# remote_switch.net
KiCad netlist of a schematic drawn in EAGLE
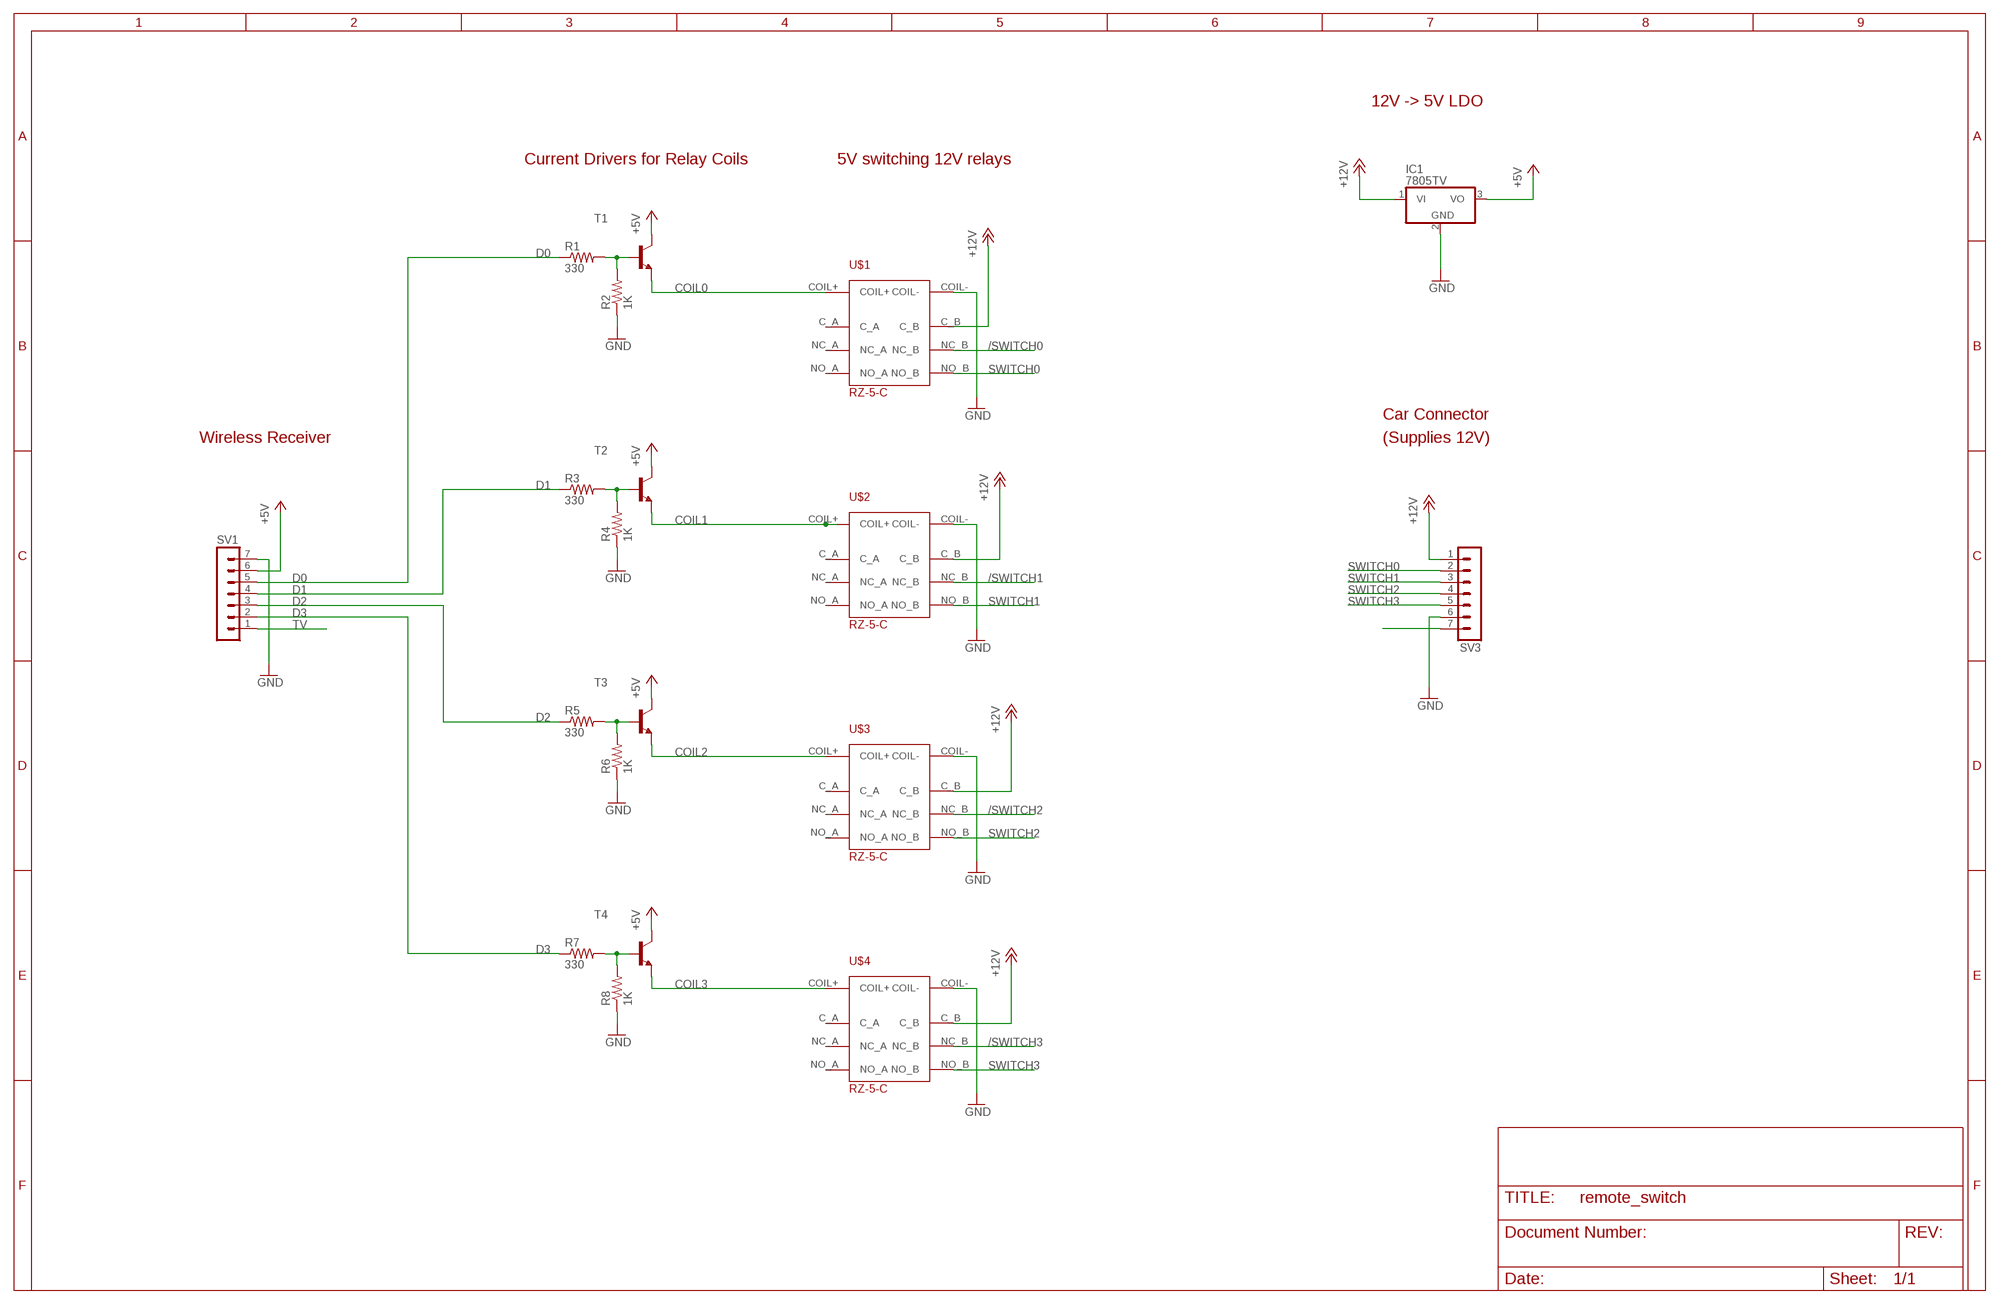
[diagram p0: schematic, sheet 1]

(export (version "E")
  (design (tool "Eeschema 10.0.6"))
  (components
    (comp (ref "IC1")
      (value "7805TV")
      (footprint "eagle-import:TO220V")
      (libsource (lib "eagle-import") (part "78TV05"))
    )
    (comp (ref "R1")
      (value "330")
      (footprint "eagle-import:P0613V")
      (libsource (lib "eagle-import") (part "R-US_0613/5V"))
    )
    (comp (ref "R2")
      (value "1K")
      (footprint "eagle-import:P0613V")
      (libsource (lib "eagle-import") (part "R-US_0613/5V"))
    )
    (comp (ref "R3")
      (value "330")
      (footprint "eagle-import:P0613V")
      (libsource (lib "eagle-import") (part "R-US_0613/5V"))
    )
    (comp (ref "R4")
      (value "1K")
      (footprint "eagle-import:P0613V")
      (libsource (lib "eagle-import") (part "R-US_0613/5V"))
    )
    (comp (ref "R5")
      (value "330")
      (footprint "eagle-import:P0613V")
      (libsource (lib "eagle-import") (part "R-US_0613/5V"))
    )
    (comp (ref "R6")
      (value "1K")
      (footprint "eagle-import:P0613V")
      (libsource (lib "eagle-import") (part "R-US_0613/5V"))
    )
    (comp (ref "R7")
      (value "330")
      (footprint "eagle-import:P0613V")
      (libsource (lib "eagle-import") (part "R-US_0613/5V"))
    )
    (comp (ref "R8")
      (value "1K")
      (footprint "eagle-import:P0613V")
      (libsource (lib "eagle-import") (part "R-US_0613/5V"))
    )
    (comp (ref "SV1")
      (value "MA07-1")
      (footprint "eagle-import:MA07-1")
      (libsource (lib "eagle-import") (part "MA07-1"))
    )
    (comp (ref "SV3")
      (value "MA07-1")
      (footprint "eagle-import:MA07-1")
      (libsource (lib "eagle-import") (part "MA07-1"))
    )
    (comp (ref "T1")
      (value "MPS2222A-NPN-TO92-CBE")
      (footprint "eagle-import:TO92-CBE")
      (libsource (lib "eagle-import") (part "-NPN-TO92-CBEMPS2222A"))
    )
    (comp (ref "T2")
      (value "MPS2222A-NPN-TO92-CBE")
      (footprint "eagle-import:TO92-CBE")
      (libsource (lib "eagle-import") (part "-NPN-TO92-CBEMPS2222A"))
    )
    (comp (ref "T3")
      (value "MPS2222A-NPN-TO92-CBE")
      (footprint "eagle-import:TO92-CBE")
      (libsource (lib "eagle-import") (part "-NPN-TO92-CBEMPS2222A"))
    )
    (comp (ref "T4")
      (value "MPS2222A-NPN-TO92-CBE")
      (footprint "eagle-import:TO92-CBE")
      (libsource (lib "eagle-import") (part "-NPN-TO92-CBEMPS2222A"))
    )
    (comp (ref "U$1")
      (value "RZ-5-C")
      (footprint "eagle-import:RZ-5-C")
      (libsource (lib "eagle-import") (part "RZ-5-C"))
    )
    (comp (ref "U$2")
      (value "RZ-5-C")
      (footprint "eagle-import:RZ-5-C")
      (libsource (lib "eagle-import") (part "RZ-5-C"))
    )
    (comp (ref "U$3")
      (value "RZ-5-C")
      (footprint "eagle-import:RZ-5-C")
      (libsource (lib "eagle-import") (part "RZ-5-C"))
    )
    (comp (ref "U$4")
      (value "RZ-5-C")
      (footprint "eagle-import:RZ-5-C")
      (libsource (lib "eagle-import") (part "RZ-5-C"))
    )
  )
  (nets
    (net (code "1") (name "+5V") (class "Default")
      (node (ref "IC1") (pin "3") (pinfunction "VO_3") (pintype "passive"))
      (node (ref "SV1") (pin "6") (pinfunction "6_6") (pintype "passive"))
      (node (ref "T1") (pin "C") (pinfunction "C_C") (pintype "passive"))
      (node (ref "T2") (pin "C") (pinfunction "C_C") (pintype "passive"))
      (node (ref "T3") (pin "C") (pinfunction "C_C") (pintype "passive"))
      (node (ref "T4") (pin "C") (pinfunction "C_C") (pintype "passive"))
    )
    (net (code "2") (name "+12V") (class "Default")
      (node (ref "IC1") (pin "1") (pinfunction "VI_1") (pintype "input"))
      (node (ref "SV3") (pin "1") (pinfunction "1_1") (pintype "passive"))
      (node (ref "U$1") (pin "C_B") (pinfunction "C_B_C_B") (pintype "bidirectional"))
      (node (ref "U$2") (pin "C_B") (pinfunction "C_B_C_B") (pintype "bidirectional"))
      (node (ref "U$3") (pin "C_B") (pinfunction "C_B_C_B") (pintype "bidirectional"))
      (node (ref "U$4") (pin "C_B") (pinfunction "C_B_C_B") (pintype "bidirectional"))
    )
    (net (code "3") (name "/COIL0") (class "Default")
      (node (ref "T1") (pin "E") (pinfunction "E_E") (pintype "passive"))
      (node (ref "U$1") (pin "COIL+") (pinfunction "COIL+_COIL+") (pintype "bidirectional"))
    )
    (net (code "4") (name "/COIL1") (class "Default")
      (node (ref "T2") (pin "E") (pinfunction "E_E") (pintype "passive"))
      (node (ref "U$2") (pin "COIL+") (pinfunction "COIL+_COIL+") (pintype "bidirectional"))
    )
    (net (code "5") (name "/COIL2") (class "Default")
      (node (ref "T3") (pin "E") (pinfunction "E_E") (pintype "passive"))
      (node (ref "U$3") (pin "COIL+") (pinfunction "COIL+_COIL+") (pintype "bidirectional"))
    )
    (net (code "6") (name "/COIL3") (class "Default")
      (node (ref "T4") (pin "E") (pinfunction "E_E") (pintype "passive"))
      (node (ref "U$4") (pin "COIL+") (pinfunction "COIL+_COIL+") (pintype "bidirectional"))
    )
    (net (code "7") (name "/D0") (class "Default")
      (node (ref "R1") (pin "1") (pinfunction "1_1") (pintype "passive"))
      (node (ref "SV1") (pin "5") (pinfunction "5_5") (pintype "passive"))
    )
    (net (code "8") (name "/D1") (class "Default")
      (node (ref "R3") (pin "1") (pinfunction "1_1") (pintype "passive"))
      (node (ref "SV1") (pin "4") (pinfunction "4_4") (pintype "passive"))
    )
    (net (code "9") (name "/D2") (class "Default")
      (node (ref "R5") (pin "1") (pinfunction "1_1") (pintype "passive"))
      (node (ref "SV1") (pin "3") (pinfunction "3_3") (pintype "passive"))
    )
    (net (code "10") (name "/D3") (class "Default")
      (node (ref "R7") (pin "1") (pinfunction "1_1") (pintype "passive"))
      (node (ref "SV1") (pin "2") (pinfunction "2_2") (pintype "passive"))
    )
    (net (code "11") (name "/SWITCH0") (class "Default")
      (node (ref "SV3") (pin "2") (pinfunction "2_2") (pintype "passive"))
      (node (ref "U$1") (pin "NO_B") (pinfunction "NO_B_NO_B") (pintype "bidirectional"))
    )
    (net (code "12") (name "/SWITCH1") (class "Default")
      (node (ref "SV3") (pin "3") (pinfunction "3_3") (pintype "passive"))
      (node (ref "U$2") (pin "NO_B") (pinfunction "NO_B_NO_B") (pintype "bidirectional"))
    )
    (net (code "13") (name "/SWITCH2") (class "Default")
      (node (ref "SV3") (pin "4") (pinfunction "4_4") (pintype "passive"))
      (node (ref "U$3") (pin "NO_B") (pinfunction "NO_B_NO_B") (pintype "bidirectional"))
    )
    (net (code "14") (name "/SWITCH3") (class "Default")
      (node (ref "SV3") (pin "5") (pinfunction "5_5") (pintype "passive"))
      (node (ref "U$4") (pin "NO_B") (pinfunction "NO_B_NO_B") (pintype "bidirectional"))
    )
    (net (code "15") (name "/TV") (class "Default")
      (node (ref "SV1") (pin "1") (pinfunction "1_1") (pintype "passive"))
    )
    (net (code "16") (name "/{slash}SWITCH0") (class "Default")
      (node (ref "U$1") (pin "NC_B") (pinfunction "NC_B_NC_B") (pintype "bidirectional"))
    )
    (net (code "17") (name "/{slash}SWITCH1") (class "Default")
      (node (ref "U$2") (pin "NC_B") (pinfunction "NC_B_NC_B") (pintype "bidirectional"))
    )
    (net (code "18") (name "/{slash}SWITCH2") (class "Default")
      (node (ref "U$3") (pin "NC_B") (pinfunction "NC_B_NC_B") (pintype "bidirectional"))
    )
    (net (code "19") (name "/{slash}SWITCH3") (class "Default")
      (node (ref "U$4") (pin "NC_B") (pinfunction "NC_B_NC_B") (pintype "bidirectional"))
    )
    (net (code "20") (name "GND") (class "Default")
      (node (ref "IC1") (pin "2") (pinfunction "GND_2") (pintype "passive"))
      (node (ref "R2") (pin "1") (pinfunction "1_1") (pintype "passive"))
      (node (ref "R4") (pin "1") (pinfunction "1_1") (pintype "passive"))
      (node (ref "R6") (pin "1") (pinfunction "1_1") (pintype "passive"))
      (node (ref "R8") (pin "1") (pinfunction "1_1") (pintype "passive"))
      (node (ref "SV1") (pin "7") (pinfunction "7_7") (pintype "passive"))
      (node (ref "SV3") (pin "6") (pinfunction "6_6") (pintype "passive"))
      (node (ref "U$1") (pin "COIL-") (pinfunction "COIL-_COIL-") (pintype "bidirectional"))
      (node (ref "U$2") (pin "COIL-") (pinfunction "COIL-_COIL-") (pintype "bidirectional"))
      (node (ref "U$3") (pin "COIL-") (pinfunction "COIL-_COIL-") (pintype "bidirectional"))
      (node (ref "U$4") (pin "COIL-") (pinfunction "COIL-_COIL-") (pintype "bidirectional"))
    )
    (net (code "21") (name "Net-(R1-Pad2)") (class "Default")
      (node (ref "R1") (pin "2") (pinfunction "2_2") (pintype "passive"))
      (node (ref "R2") (pin "2") (pinfunction "2_2") (pintype "passive"))
      (node (ref "T1") (pin "B") (pinfunction "B_B") (pintype "passive"))
    )
    (net (code "22") (name "Net-(R3-Pad2)") (class "Default")
      (node (ref "R3") (pin "2") (pinfunction "2_2") (pintype "passive"))
      (node (ref "R4") (pin "2") (pinfunction "2_2") (pintype "passive"))
      (node (ref "T2") (pin "B") (pinfunction "B_B") (pintype "passive"))
    )
    (net (code "23") (name "Net-(R5-Pad2)") (class "Default")
      (node (ref "R5") (pin "2") (pinfunction "2_2") (pintype "passive"))
      (node (ref "R6") (pin "2") (pinfunction "2_2") (pintype "passive"))
      (node (ref "T3") (pin "B") (pinfunction "B_B") (pintype "passive"))
    )
    (net (code "24") (name "Net-(R7-Pad2)") (class "Default")
      (node (ref "R7") (pin "2") (pinfunction "2_2") (pintype "passive"))
      (node (ref "R8") (pin "2") (pinfunction "2_2") (pintype "passive"))
      (node (ref "T4") (pin "B") (pinfunction "B_B") (pintype "passive"))
    )
    (net (code "25") (name "unconnected-(SV3-Pad7)") (class "Default")
      (node (ref "SV3") (pin "7") (pinfunction "7_7") (pintype "passive"))
    )
    (net (code "26") (name "unconnected-(U$1-PadC_A)") (class "Default")
      (node (ref "U$1") (pin "C_A") (pinfunction "C_A_C_A") (pintype "bidirectional"))
    )
    (net (code "27") (name "unconnected-(U$1-PadNC_A)") (class "Default")
      (node (ref "U$1") (pin "NC_A") (pinfunction "NC_A_NC_A") (pintype "bidirectional"))
    )
    (net (code "28") (name "unconnected-(U$1-PadNO_A)") (class "Default")
      (node (ref "U$1") (pin "NO_A") (pinfunction "NO_A_NO_A") (pintype "bidirectional"))
    )
    (net (code "29") (name "unconnected-(U$2-PadC_A)") (class "Default")
      (node (ref "U$2") (pin "C_A") (pinfunction "C_A_C_A") (pintype "bidirectional"))
    )
    (net (code "30") (name "unconnected-(U$2-PadNC_A)") (class "Default")
      (node (ref "U$2") (pin "NC_A") (pinfunction "NC_A_NC_A") (pintype "bidirectional"))
    )
    (net (code "31") (name "unconnected-(U$2-PadNO_A)") (class "Default")
      (node (ref "U$2") (pin "NO_A") (pinfunction "NO_A_NO_A") (pintype "bidirectional"))
    )
    (net (code "32") (name "unconnected-(U$3-PadC_A)") (class "Default")
      (node (ref "U$3") (pin "C_A") (pinfunction "C_A_C_A") (pintype "bidirectional"))
    )
    (net (code "33") (name "unconnected-(U$3-PadNC_A)") (class "Default")
      (node (ref "U$3") (pin "NC_A") (pinfunction "NC_A_NC_A") (pintype "bidirectional"))
    )
    (net (code "34") (name "unconnected-(U$3-PadNO_A)") (class "Default")
      (node (ref "U$3") (pin "NO_A") (pinfunction "NO_A_NO_A") (pintype "bidirectional"))
    )
    (net (code "35") (name "unconnected-(U$4-PadC_A)") (class "Default")
      (node (ref "U$4") (pin "C_A") (pinfunction "C_A_C_A") (pintype "bidirectional"))
    )
    (net (code "36") (name "unconnected-(U$4-PadNC_A)") (class "Default")
      (node (ref "U$4") (pin "NC_A") (pinfunction "NC_A_NC_A") (pintype "bidirectional"))
    )
    (net (code "37") (name "unconnected-(U$4-PadNO_A)") (class "Default")
      (node (ref "U$4") (pin "NO_A") (pinfunction "NO_A_NO_A") (pintype "bidirectional"))
    )
  )
)
